# DM_V1_power.net
KiCad netlist of a schematic drawn in Altium Designer
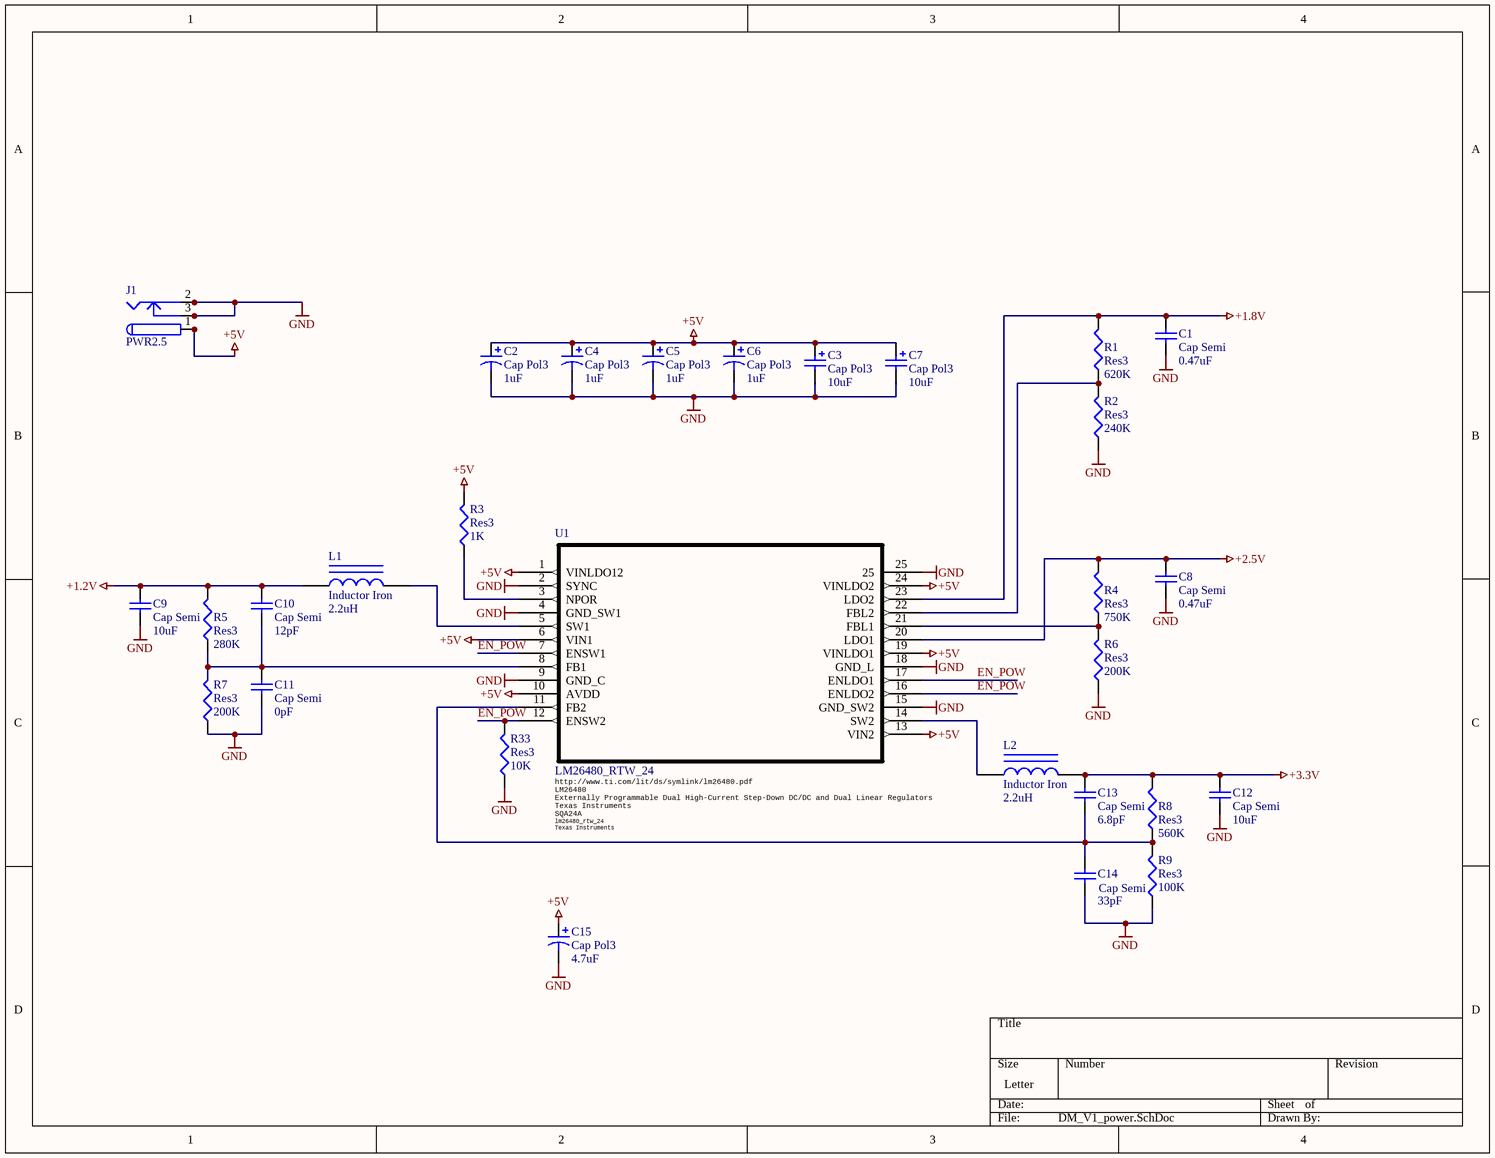
[diagram p0: DM_V1_power.SchDoc]

(export (version "E")
  (design (tool "Eeschema 10.0.6"))
  (components
    (comp (ref "C1")
      (value "Cap Semi")
      (footprint "C0805")
      (description "Capacitor (Semiconductor SIM Model)")
      (fields (field (name "ALTIUM_VALUE") "0.47uF") (field (name "PUBLISHER") "Altium Limited"))
      (libsource (lib "Miscellaneous Devices") (part "Cap Semi"))
    )
    (comp (ref "C2")
      (value "Cap Pol3")
      (footprint "C1206")
      (description "Polarized Capacitor (Surface Mount)")
      (fields (field (name "ALTIUM_VALUE") "1uF") (field (name "PUBLISHER") "Altium Limited"))
      (libsource (lib "Miscellaneous Devices") (part "Cap Pol3"))
    )
    (comp (ref "C3")
      (value "Cap Pol3")
      (footprint "C1206")
      (description "Polarized Capacitor (Surface Mount)")
      (fields (field (name "ALTIUM_VALUE") "10uF") (field (name "PUBLISHER") "Altium Limited"))
      (libsource (lib "") (part "Cap Pol3_1"))
    )
    (comp (ref "C4")
      (value "Cap Pol3")
      (footprint "C1206")
      (description "Polarized Capacitor (Surface Mount)")
      (fields (field (name "ALTIUM_VALUE") "1uF") (field (name "PUBLISHER") "Altium Limited"))
      (libsource (lib "Miscellaneous Devices") (part "Cap Pol3"))
    )
    (comp (ref "C5")
      (value "Cap Pol3")
      (footprint "C1206")
      (description "Polarized Capacitor (Surface Mount)")
      (fields (field (name "ALTIUM_VALUE") "1uF") (field (name "PUBLISHER") "Altium Limited"))
      (libsource (lib "Miscellaneous Devices") (part "Cap Pol3"))
    )
    (comp (ref "C6")
      (value "Cap Pol3")
      (footprint "C1206")
      (description "Polarized Capacitor (Surface Mount)")
      (fields (field (name "ALTIUM_VALUE") "1uF") (field (name "PUBLISHER") "Altium Limited"))
      (libsource (lib "Miscellaneous Devices") (part "Cap Pol3"))
    )
    (comp (ref "C7")
      (value "Cap Pol3")
      (footprint "C1206")
      (description "Polarized Capacitor (Surface Mount)")
      (fields (field (name "ALTIUM_VALUE") "10uF") (field (name "PUBLISHER") "Altium Limited"))
      (libsource (lib "") (part "Cap Pol3_1"))
    )
    (comp (ref "C8")
      (value "Cap Semi")
      (footprint "C0805")
      (description "Capacitor (Semiconductor SIM Model)")
      (fields (field (name "ALTIUM_VALUE") "0.47uF") (field (name "PUBLISHER") "Altium Limited"))
      (libsource (lib "Miscellaneous Devices") (part "Cap Semi"))
    )
    (comp (ref "C9")
      (value "Cap Semi")
      (footprint "C0805")
      (description "Capacitor (Semiconductor SIM Model)")
      (fields (field (name "ALTIUM_VALUE") "10uF") (field (name "PUBLISHER") "Altium Limited"))
      (libsource (lib "Miscellaneous Devices") (part "Cap Semi"))
    )
    (comp (ref "C10")
      (value "Cap Semi")
      (footprint "C0805")
      (description "Capacitor (Semiconductor SIM Model)")
      (fields (field (name "ALTIUM_VALUE") "12pF") (field (name "PUBLISHER") "Altium Limited"))
      (libsource (lib "Miscellaneous Devices") (part "Cap Semi"))
    )
    (comp (ref "C11")
      (value "Cap Semi")
      (footprint "C0805")
      (description "Capacitor (Semiconductor SIM Model)")
      (fields (field (name "ALTIUM_VALUE") "0pF") (field (name "PUBLISHER") "Altium Limited"))
      (libsource (lib "Miscellaneous Devices") (part "Cap Semi"))
    )
    (comp (ref "C12")
      (value "Cap Semi")
      (footprint "C0805")
      (description "Capacitor (Semiconductor SIM Model)")
      (fields (field (name "ALTIUM_VALUE") "10uF") (field (name "PUBLISHER") "Altium Limited"))
      (libsource (lib "Miscellaneous Devices") (part "Cap Semi"))
    )
    (comp (ref "C13")
      (value "Cap Semi")
      (footprint "C0805")
      (description "Capacitor (Semiconductor SIM Model)")
      (fields (field (name "ALTIUM_VALUE") "6.8pF") (field (name "PUBLISHER") "Altium Limited"))
      (libsource (lib "Miscellaneous Devices") (part "Cap Semi"))
    )
    (comp (ref "C14")
      (value "Cap Semi")
      (footprint "C0805")
      (description "Capacitor (Semiconductor SIM Model)")
      (fields (field (name "ALTIUM_VALUE") "33pF") (field (name "PUBLISHER") "Altium Limited"))
      (libsource (lib "Miscellaneous Devices") (part "Cap Semi"))
    )
    (comp (ref "C15")
      (value "Cap Pol3")
      (footprint "C1206")
      (description "Polarized Capacitor (Surface Mount)")
      (fields (field (name "ALTIUM_VALUE") "4.7uF") (field (name "PUBLISHER") "Altium Limited"))
      (libsource (lib "Miscellaneous Devices") (part "Cap Pol3"))
    )
    (comp (ref "J1")
      (value "PWR2.5")
      (footprint "KLD-0202")
      (description "Low Voltage Power Supply Connector")
      (fields (field (name "PUBLISHER") "Altium Limited"))
      (libsource (lib "Miscellaneous Connectors") (part "PWR2.5"))
    )
    (comp (ref "L1")
      (value "Inductor Iron")
      (footprint "Coil inductor")
      (description "Magnetic-Core Inductor")
      (fields (field (name "ALTIUM_VALUE") "2.2uH") (field (name "PUBLISHER") "Altium Limited"))
      (libsource (lib "Miscellaneous Devices") (part "Inductor Iron"))
    )
    (comp (ref "L2")
      (value "Inductor Iron")
      (footprint "Coil inductor")
      (description "Magnetic-Core Inductor")
      (fields (field (name "ALTIUM_VALUE") "2.2uH") (field (name "PUBLISHER") "Altium Limited"))
      (libsource (lib "Miscellaneous Devices") (part "Inductor Iron"))
    )
    (comp (ref "R1")
      (value "Res3")
      (footprint "J1-0603")
      (description "Resistor")
      (fields (field (name "ALTIUM_VALUE") "620K") (field (name "PUBLISHER") "Altium Limited"))
      (libsource (lib "Miscellaneous Devices") (part "Res3"))
    )
    (comp (ref "R2")
      (value "Res3")
      (footprint "J1-0603")
      (description "Resistor")
      (fields (field (name "ALTIUM_VALUE") "240K") (field (name "PUBLISHER") "Altium Limited"))
      (libsource (lib "Miscellaneous Devices") (part "Res3"))
    )
    (comp (ref "R3")
      (value "Res3")
      (footprint "J1-0603")
      (description "Resistor")
      (fields (field (name "ALTIUM_VALUE") "1K") (field (name "PUBLISHER") "Altium Limited"))
      (libsource (lib "Miscellaneous Devices") (part "Res3"))
    )
    (comp (ref "R4")
      (value "Res3")
      (footprint "J1-0603")
      (description "Resistor")
      (fields (field (name "ALTIUM_VALUE") "750K") (field (name "PUBLISHER") "Altium Limited"))
      (libsource (lib "Miscellaneous Devices") (part "Res3"))
    )
    (comp (ref "R5")
      (value "Res3")
      (footprint "J1-0603")
      (description "Resistor")
      (fields (field (name "ALTIUM_VALUE") "280K") (field (name "PUBLISHER") "Altium Limited"))
      (libsource (lib "Miscellaneous Devices") (part "Res3"))
    )
    (comp (ref "R6")
      (value "Res3")
      (footprint "J1-0603")
      (description "Resistor")
      (fields (field (name "ALTIUM_VALUE") "200K") (field (name "PUBLISHER") "Altium Limited"))
      (libsource (lib "Miscellaneous Devices") (part "Res3"))
    )
    (comp (ref "R7")
      (value "Res3")
      (footprint "J1-0603")
      (description "Resistor")
      (fields (field (name "ALTIUM_VALUE") "200K") (field (name "PUBLISHER") "Altium Limited"))
      (libsource (lib "Miscellaneous Devices") (part "Res3"))
    )
    (comp (ref "R8")
      (value "Res3")
      (footprint "J1-0603")
      (description "Resistor")
      (fields (field (name "ALTIUM_VALUE") "560K") (field (name "PUBLISHER") "Altium Limited"))
      (libsource (lib "Miscellaneous Devices") (part "Res3"))
    )
    (comp (ref "R9")
      (value "Res3")
      (footprint "J1-0603")
      (description "Resistor")
      (fields (field (name "ALTIUM_VALUE") "100K") (field (name "PUBLISHER") "Altium Limited"))
      (libsource (lib "Miscellaneous Devices") (part "Res3"))
    )
    (comp (ref "R33")
      (value "Res3")
      (footprint "J1-0603")
      (description "Resistor")
      (fields (field (name "ALTIUM_VALUE") "10K") (field (name "PUBLISHER") "Altium Limited"))
      (libsource (lib "Miscellaneous Devices") (part "Res3"))
    )
    (comp (ref "U1")
      (value "LM26480_RTW_24")
      (footprint "SQA24A")
      (description "Externally Programmable Dual High-Current Step-Down DC/DC and Dual Linear Regulators")
      (fields
        (field (name "DATASHEETURL") "http://www.ti.com/lit/ds/symlink/lm26480.pdf")
        (field (name "BASEPN") "LM26480")
        (field (name "MANUFACTURER") "Texas Instruments")
        (field (name "NSC_PACKAGEREFERENCE") "SQA24A")
        (field (name "MANUFACTURER_PART_NUMBER") "lm26480_rtw_24")
        (field (name "VENDOR") "Texas Instruments")
      )
      (libsource (lib "2012-07-28_19-10-40") (part "LM26480_RTW_24"))
    )
  )
  (nets
    (net (code "1") (name "+1.2V") (class "Default")
      (node (ref "C10") (pin "2") (pinfunction "2_2") (pintype "passive"))
      (node (ref "C9") (pin "2") (pinfunction "2_2") (pintype "passive"))
      (node (ref "L1") (pin "1") (pinfunction "1_1") (pintype "passive"))
      (node (ref "R5") (pin "2") (pinfunction "2_2") (pintype "passive"))
    )
    (net (code "2") (name "+1.8V") (class "Default")
      (node (ref "C1") (pin "2") (pinfunction "2_2") (pintype "passive"))
      (node (ref "R1") (pin "2") (pinfunction "2_2") (pintype "passive"))
      (node (ref "U1") (pin "23") (pinfunction "LDO2_23") (pintype "output"))
    )
    (net (code "3") (name "+2.5V") (class "Default")
      (node (ref "C8") (pin "2") (pinfunction "2_2") (pintype "passive"))
      (node (ref "R4") (pin "2") (pinfunction "2_2") (pintype "passive"))
      (node (ref "U1") (pin "20") (pinfunction "LDO1_20") (pintype "output"))
    )
    (net (code "4") (name "+3.3V") (class "Default")
      (node (ref "C12") (pin "2") (pinfunction "2_2") (pintype "passive"))
      (node (ref "C13") (pin "2") (pinfunction "2_2") (pintype "passive"))
      (node (ref "L2") (pin "2") (pinfunction "2_2") (pintype "passive"))
      (node (ref "R8") (pin "2") (pinfunction "2_2") (pintype "passive"))
    )
    (net (code "5") (name "+5V") (class "Default")
      (node (ref "C15") (pin "1") (pinfunction "1_1") (pintype "passive"))
      (node (ref "C2") (pin "1") (pinfunction "1_1") (pintype "passive"))
      (node (ref "C3") (pin "1") (pinfunction "1_1") (pintype "passive"))
      (node (ref "C4") (pin "1") (pinfunction "1_1") (pintype "passive"))
      (node (ref "C5") (pin "1") (pinfunction "1_1") (pintype "passive"))
      (node (ref "C6") (pin "1") (pinfunction "1_1") (pintype "passive"))
      (node (ref "C7") (pin "1") (pinfunction "1_1") (pintype "passive"))
      (node (ref "J1") (pin "1") (pinfunction "1_1") (pintype "power_in"))
      (node (ref "J1") (pin "1A") (pinfunction "1A_1A") (pintype "power_in"))
      (node (ref "J1") (pin "1B") (pinfunction "1B_1B") (pintype "power_in"))
      (node (ref "R3") (pin "2") (pinfunction "2_2") (pintype "passive"))
      (node (ref "U1") (pin "1") (pinfunction "VINLDO12_1") (pintype "output"))
      (node (ref "U1") (pin "10") (pinfunction "AVDD_10") (pintype "power_in"))
      (node (ref "U1") (pin "13") (pinfunction "VIN2_13") (pintype "output"))
      (node (ref "U1") (pin "19") (pinfunction "VINLDO1_19") (pintype "output"))
      (node (ref "U1") (pin "24") (pinfunction "VINLDO2_24") (pintype "output"))
      (node (ref "U1") (pin "6") (pinfunction "VIN1_6") (pintype "output"))
    )
    (net (code "6") (name "/EN_POW") (class "Default")
      (node (ref "R33") (pin "2") (pinfunction "2_2") (pintype "passive"))
      (node (ref "U1") (pin "12") (pinfunction "ENSW2_12") (pintype "output"))
      (node (ref "U1") (pin "16") (pinfunction "ENLDO2_16") (pintype "output"))
      (node (ref "U1") (pin "17") (pinfunction "ENLDO1_17") (pintype "output"))
      (node (ref "U1") (pin "7") (pinfunction "ENSW1_7") (pintype "output"))
    )
    (net (code "7") (name "GND") (class "Default")
      (node (ref "C1") (pin "1") (pinfunction "1_1") (pintype "passive"))
      (node (ref "C11") (pin "1") (pinfunction "1_1") (pintype "passive"))
      (node (ref "C12") (pin "1") (pinfunction "1_1") (pintype "passive"))
      (node (ref "C14") (pin "1") (pinfunction "1_1") (pintype "passive"))
      (node (ref "C15") (pin "2") (pinfunction "2_2") (pintype "passive"))
      (node (ref "C2") (pin "2") (pinfunction "2_2") (pintype "passive"))
      (node (ref "C3") (pin "2") (pinfunction "2_2") (pintype "passive"))
      (node (ref "C4") (pin "2") (pinfunction "2_2") (pintype "passive"))
      (node (ref "C5") (pin "2") (pinfunction "2_2") (pintype "passive"))
      (node (ref "C6") (pin "2") (pinfunction "2_2") (pintype "passive"))
      (node (ref "C7") (pin "2") (pinfunction "2_2") (pintype "passive"))
      (node (ref "C8") (pin "1") (pinfunction "1_1") (pintype "passive"))
      (node (ref "C9") (pin "1") (pinfunction "1_1") (pintype "passive"))
      (node (ref "J1") (pin "2") (pinfunction "2_2") (pintype "power_in"))
      (node (ref "J1") (pin "2A") (pinfunction "2A_2A") (pintype "power_in"))
      (node (ref "J1") (pin "2B") (pinfunction "2B_2B") (pintype "power_in"))
      (node (ref "J1") (pin "3") (pinfunction "3_3") (pintype "power_in"))
      (node (ref "J1") (pin "3A") (pinfunction "3A_3A") (pintype "power_in"))
      (node (ref "J1") (pin "3B") (pinfunction "3B_3B") (pintype "power_in"))
      (node (ref "R2") (pin "1") (pinfunction "1_1") (pintype "passive"))
      (node (ref "R33") (pin "1") (pinfunction "1_1") (pintype "passive"))
      (node (ref "R6") (pin "1") (pinfunction "1_1") (pintype "passive"))
      (node (ref "R7") (pin "1") (pinfunction "1_1") (pintype "passive"))
      (node (ref "R9") (pin "1") (pinfunction "1_1") (pintype "passive"))
      (node (ref "U1") (pin "15") (pinfunction "GND_SW2_15") (pintype "power_in"))
      (node (ref "U1") (pin "18") (pinfunction "GND_L_18") (pintype "power_in"))
      (node (ref "U1") (pin "2") (pinfunction "SYNC_2") (pintype "output"))
      (node (ref "U1") (pin "25") (pinfunction "25_25") (pintype "passive"))
      (node (ref "U1") (pin "4") (pinfunction "GND_SW1_4") (pintype "power_in"))
      (node (ref "U1") (pin "9") (pinfunction "GND_C_9") (pintype "power_in"))
    )
    (net (code "8") (name "Net-(U1-FB1)") (class "Default")
      (node (ref "C10") (pin "1") (pinfunction "1_1") (pintype "passive"))
      (node (ref "C11") (pin "2") (pinfunction "2_2") (pintype "passive"))
      (node (ref "R5") (pin "1") (pinfunction "1_1") (pintype "passive"))
      (node (ref "R7") (pin "2") (pinfunction "2_2") (pintype "passive"))
      (node (ref "U1") (pin "8") (pinfunction "FB1_8") (pintype "output"))
    )
    (net (code "9") (name "Net-(U1-FB2)") (class "Default")
      (node (ref "C13") (pin "1") (pinfunction "1_1") (pintype "passive"))
      (node (ref "C14") (pin "2") (pinfunction "2_2") (pintype "passive"))
      (node (ref "R8") (pin "1") (pinfunction "1_1") (pintype "passive"))
      (node (ref "R9") (pin "2") (pinfunction "2_2") (pintype "passive"))
      (node (ref "U1") (pin "11") (pinfunction "FB2_11") (pintype "output"))
    )
    (net (code "10") (name "Net-(U1-FBL1)") (class "Default")
      (node (ref "R4") (pin "1") (pinfunction "1_1") (pintype "passive"))
      (node (ref "R6") (pin "2") (pinfunction "2_2") (pintype "passive"))
      (node (ref "U1") (pin "21") (pinfunction "FBL1_21") (pintype "output"))
    )
    (net (code "11") (name "Net-(U1-FBL2)") (class "Default")
      (node (ref "R1") (pin "1") (pinfunction "1_1") (pintype "passive"))
      (node (ref "R2") (pin "2") (pinfunction "2_2") (pintype "passive"))
      (node (ref "U1") (pin "22") (pinfunction "FBL2_22") (pintype "output"))
    )
    (net (code "12") (name "Net-(U1-NPOR)") (class "Default")
      (node (ref "R3") (pin "1") (pinfunction "1_1") (pintype "passive"))
      (node (ref "U1") (pin "3") (pinfunction "NPOR_3") (pintype "output"))
    )
    (net (code "13") (name "Net-(U1-SW1)") (class "Default")
      (node (ref "L1") (pin "2") (pinfunction "2_2") (pintype "passive"))
      (node (ref "U1") (pin "5") (pinfunction "SW1_5") (pintype "output"))
    )
    (net (code "14") (name "Net-(U1-SW2)") (class "Default")
      (node (ref "L2") (pin "1") (pinfunction "1_1") (pintype "passive"))
      (node (ref "U1") (pin "14") (pinfunction "SW2_14") (pintype "output"))
    )
  )
)
